# headamp.net
KiCad netlist of a schematic drawn in EAGLE
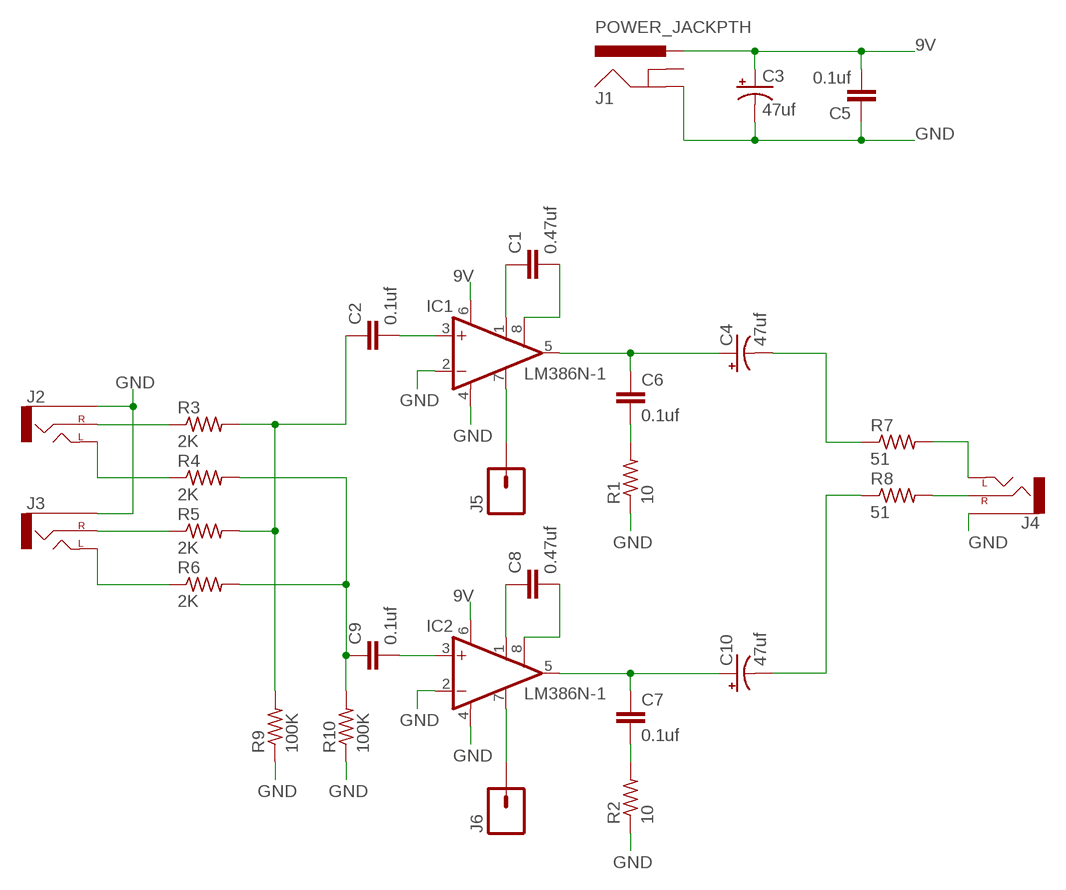
[diagram p0: schematic, sheet 1]

(export (version "E")
  (design (tool "Eeschema 10.0.6"))
  (components
    (comp (ref "C1")
      (value "0.47uf")
      (footprint "eagle-import:1210")
      (libsource (lib "eagle-import") (part "10UF50V20%(1210)"))
    )
    (comp (ref "C2")
      (value "0.1uf")
      (footprint "eagle-import:1210")
      (libsource (lib "eagle-import") (part "10UF50V20%(1210)"))
    )
    (comp (ref "C3")
      (value "47uf")
      (footprint "eagle-import:CPOL-RADIAL-100UF-25V")
      (libsource (lib "eagle-import") (part "100UF-25V-20%(PTH)"))
    )
    (comp (ref "C4")
      (value "47uf")
      (footprint "eagle-import:CPOL-RADIAL-100UF-25V")
      (libsource (lib "eagle-import") (part "100UF-25V-20%(PTH)"))
    )
    (comp (ref "C5")
      (value "0.1uf")
      (footprint "eagle-import:1210")
      (libsource (lib "eagle-import") (part "10UF50V20%(1210)"))
    )
    (comp (ref "C6")
      (value "0.1uf")
      (footprint "eagle-import:1210")
      (libsource (lib "eagle-import") (part "10UF50V20%(1210)"))
    )
    (comp (ref "C7")
      (value "0.1uf")
      (footprint "eagle-import:1210")
      (libsource (lib "eagle-import") (part "10UF50V20%(1210)"))
    )
    (comp (ref "C8")
      (value "0.47uf")
      (footprint "eagle-import:1210")
      (libsource (lib "eagle-import") (part "10UF50V20%(1210)"))
    )
    (comp (ref "C9")
      (value "0.1uf")
      (footprint "eagle-import:1210")
      (libsource (lib "eagle-import") (part "10UF50V20%(1210)"))
    )
    (comp (ref "C10")
      (value "47uf")
      (footprint "eagle-import:CPOL-RADIAL-100UF-25V")
      (libsource (lib "eagle-import") (part "100UF-25V-20%(PTH)"))
    )
    (comp (ref "IC1")
      (value "LM386N-1")
      (footprint "eagle-import:DIL08")
      (libsource (lib "eagle-import") (part "LM386?-N1"))
    )
    (comp (ref "IC2")
      (value "LM386N-1")
      (footprint "eagle-import:DIL08")
      (libsource (lib "eagle-import") (part "LM386?-N1"))
    )
    (comp (ref "J1")
      (value "POWER_JACKPTH")
      (footprint "eagle-import:POWER_JACK_PTH")
      (libsource (lib "eagle-import") (part "POWER_JACKPTH"))
    )
    (comp (ref "J2")
      (value "AUDIO-JACKPTH")
      (footprint "eagle-import:AUDIO-JACK")
      (libsource (lib "eagle-import") (part "AUDIO-JACKPTH"))
    )
    (comp (ref "J3")
      (value "AUDIO-JACKPTH")
      (footprint "eagle-import:AUDIO-JACK")
      (libsource (lib "eagle-import") (part "AUDIO-JACKPTH"))
    )
    (comp (ref "J4")
      (value "AUDIO-JACKPTH")
      (footprint "eagle-import:AUDIO-JACK")
      (libsource (lib "eagle-import") (part "AUDIO-JACKPTH"))
    )
    (comp (ref "J5")
      (value "M01NOSILK-KIT")
      (footprint "eagle-import:1X01NS-KIT")
      (libsource (lib "eagle-import") (part "M01NOSILK-KIT"))
    )
    (comp (ref "J6")
      (value "M01NOSILK-KIT")
      (footprint "eagle-import:1X01NS-KIT")
      (libsource (lib "eagle-import") (part "M01NOSILK-KIT"))
    )
    (comp (ref "R1")
      (value "10")
      (footprint "eagle-import:M0805")
      (libsource (lib "eagle-import") (part "R-US_M0805"))
    )
    (comp (ref "R2")
      (value "10")
      (footprint "eagle-import:M0805")
      (libsource (lib "eagle-import") (part "R-US_M0805"))
    )
    (comp (ref "R3")
      (value "2K")
      (footprint "eagle-import:M0805")
      (libsource (lib "eagle-import") (part "R-US_M0805"))
    )
    (comp (ref "R4")
      (value "2K")
      (footprint "eagle-import:M0805")
      (libsource (lib "eagle-import") (part "R-US_M0805"))
    )
    (comp (ref "R5")
      (value "2K")
      (footprint "eagle-import:M0805")
      (libsource (lib "eagle-import") (part "R-US_M0805"))
    )
    (comp (ref "R6")
      (value "2K")
      (footprint "eagle-import:M0805")
      (libsource (lib "eagle-import") (part "R-US_M0805"))
    )
    (comp (ref "R7")
      (value "51")
      (footprint "eagle-import:M0805")
      (libsource (lib "eagle-import") (part "R-US_M0805"))
    )
    (comp (ref "R8")
      (value "51")
      (footprint "eagle-import:M0805")
      (libsource (lib "eagle-import") (part "R-US_M0805"))
    )
    (comp (ref "R9")
      (value "100K")
      (footprint "eagle-import:M0805")
      (libsource (lib "eagle-import") (part "R-US_M0805"))
    )
    (comp (ref "R10")
      (value "100K")
      (footprint "eagle-import:M0805")
      (libsource (lib "eagle-import") (part "R-US_M0805"))
    )
  )
  (nets
    (net (code "1") (name "/9V") (class "Default")
      (node (ref "C3") (pin "1") (pinfunction "+_1") (pintype "passive"))
      (node (ref "C5") (pin "2") (pinfunction "2_2") (pintype "passive"))
      (node (ref "IC1") (pin "6") (pinfunction "VS_6") (pintype "power_in"))
      (node (ref "IC2") (pin "6") (pinfunction "VS_6") (pintype "power_in"))
      (node (ref "J1") (pin "PWR") (pinfunction "PWR_PWR") (pintype "bidirectional"))
    )
    (net (code "2") (name "/GND") (class "Default")
      (node (ref "C3") (pin "2") (pinfunction "-_2") (pintype "passive"))
      (node (ref "C5") (pin "1") (pinfunction "1_1") (pintype "passive"))
      (node (ref "IC1") (pin "2") (pinfunction "-IN_2") (pintype "input"))
      (node (ref "IC1") (pin "4") (pinfunction "GND_4") (pintype "power_in"))
      (node (ref "IC2") (pin "2") (pinfunction "-IN_2") (pintype "input"))
      (node (ref "IC2") (pin "4") (pinfunction "GND_4") (pintype "power_in"))
      (node (ref "J1") (pin "GND") (pinfunction "GND_GND") (pintype "bidirectional"))
      (node (ref "J2") (pin "SLEEVE") (pinfunction "SLEEVE_SLEEVE") (pintype "bidirectional"))
      (node (ref "J3") (pin "SLEEVE") (pinfunction "SLEEVE_SLEEVE") (pintype "bidirectional"))
      (node (ref "J4") (pin "SLEEVE") (pinfunction "SLEEVE_SLEEVE") (pintype "bidirectional"))
      (node (ref "R1") (pin "1") (pinfunction "1_1") (pintype "passive"))
      (node (ref "R10") (pin "1") (pinfunction "1_1") (pintype "passive"))
      (node (ref "R2") (pin "1") (pinfunction "1_1") (pintype "passive"))
      (node (ref "R9") (pin "1") (pinfunction "1_1") (pintype "passive"))
    )
    (net (code "3") (name "Net-(C1-Pad1)") (class "Default")
      (node (ref "C1") (pin "1") (pinfunction "1_1") (pintype "passive"))
      (node (ref "IC1") (pin "1") (pinfunction "GAIN_1") (pintype "passive"))
    )
    (net (code "4") (name "Net-(C1-Pad2)") (class "Default")
      (node (ref "C1") (pin "2") (pinfunction "2_2") (pintype "passive"))
      (node (ref "IC1") (pin "8") (pinfunction "GAIN_8") (pintype "passive"))
    )
    (net (code "5") (name "Net-(C2-Pad1)") (class "Default")
      (node (ref "C2") (pin "1") (pinfunction "1_1") (pintype "passive"))
      (node (ref "R3") (pin "2") (pinfunction "2_2") (pintype "passive"))
      (node (ref "R5") (pin "2") (pinfunction "2_2") (pintype "passive"))
      (node (ref "R9") (pin "2") (pinfunction "2_2") (pintype "passive"))
    )
    (net (code "6") (name "Net-(C4-+)") (class "Default")
      (node (ref "C4") (pin "1") (pinfunction "+_1") (pintype "passive"))
      (node (ref "C6") (pin "1") (pinfunction "1_1") (pintype "passive"))
      (node (ref "IC1") (pin "5") (pinfunction "OUT_5") (pintype "output"))
    )
    (net (code "7") (name "Net-(C4--)") (class "Default")
      (node (ref "C4") (pin "2") (pinfunction "-_2") (pintype "passive"))
      (node (ref "R7") (pin "1") (pinfunction "1_1") (pintype "passive"))
    )
    (net (code "8") (name "Net-(C6-Pad2)") (class "Default")
      (node (ref "C6") (pin "2") (pinfunction "2_2") (pintype "passive"))
      (node (ref "R1") (pin "2") (pinfunction "2_2") (pintype "passive"))
    )
    (net (code "9") (name "Net-(C7-Pad2)") (class "Default")
      (node (ref "C7") (pin "2") (pinfunction "2_2") (pintype "passive"))
      (node (ref "R2") (pin "2") (pinfunction "2_2") (pintype "passive"))
    )
    (net (code "10") (name "Net-(C8-Pad1)") (class "Default")
      (node (ref "C8") (pin "1") (pinfunction "1_1") (pintype "passive"))
      (node (ref "IC2") (pin "1") (pinfunction "GAIN_1") (pintype "passive"))
    )
    (net (code "11") (name "Net-(C8-Pad2)") (class "Default")
      (node (ref "C8") (pin "2") (pinfunction "2_2") (pintype "passive"))
      (node (ref "IC2") (pin "8") (pinfunction "GAIN_8") (pintype "passive"))
    )
    (net (code "12") (name "Net-(C9-Pad1)") (class "Default")
      (node (ref "C9") (pin "1") (pinfunction "1_1") (pintype "passive"))
      (node (ref "R10") (pin "2") (pinfunction "2_2") (pintype "passive"))
      (node (ref "R4") (pin "2") (pinfunction "2_2") (pintype "passive"))
      (node (ref "R6") (pin "2") (pinfunction "2_2") (pintype "passive"))
    )
    (net (code "13") (name "Net-(C10-+)") (class "Default")
      (node (ref "C10") (pin "1") (pinfunction "+_1") (pintype "passive"))
      (node (ref "C7") (pin "1") (pinfunction "1_1") (pintype "passive"))
      (node (ref "IC2") (pin "5") (pinfunction "OUT_5") (pintype "output"))
    )
    (net (code "14") (name "Net-(C10--)") (class "Default")
      (node (ref "C10") (pin "2") (pinfunction "-_2") (pintype "passive"))
      (node (ref "R8") (pin "1") (pinfunction "1_1") (pintype "passive"))
    )
    (net (code "15") (name "Net-(IC1-+IN)") (class "Default")
      (node (ref "C2") (pin "2") (pinfunction "2_2") (pintype "passive"))
      (node (ref "IC1") (pin "3") (pinfunction "+IN_3") (pintype "input"))
    )
    (net (code "16") (name "Net-(IC1-BYPASS)") (class "Default")
      (node (ref "IC1") (pin "7") (pinfunction "BYPASS_7") (pintype "passive"))
      (node (ref "J5") (pin "1") (pinfunction "1_1") (pintype "passive"))
    )
    (net (code "17") (name "Net-(IC2-+IN)") (class "Default")
      (node (ref "C9") (pin "2") (pinfunction "2_2") (pintype "passive"))
      (node (ref "IC2") (pin "3") (pinfunction "+IN_3") (pintype "input"))
    )
    (net (code "18") (name "Net-(IC2-BYPASS)") (class "Default")
      (node (ref "IC2") (pin "7") (pinfunction "BYPASS_7") (pintype "passive"))
      (node (ref "J6") (pin "1") (pinfunction "1_1") (pintype "passive"))
    )
    (net (code "19") (name "Net-(J2-LEFT)") (class "Default")
      (node (ref "J2") (pin "TIP") (pinfunction "LEFT_TIP") (pintype "bidirectional"))
      (node (ref "R4") (pin "1") (pinfunction "1_1") (pintype "passive"))
    )
    (net (code "20") (name "Net-(J2-RIGHT)") (class "Default")
      (node (ref "J2") (pin "RING") (pinfunction "RIGHT_RING") (pintype "bidirectional"))
      (node (ref "R3") (pin "1") (pinfunction "1_1") (pintype "passive"))
    )
    (net (code "21") (name "Net-(J3-LEFT)") (class "Default")
      (node (ref "J3") (pin "TIP") (pinfunction "LEFT_TIP") (pintype "bidirectional"))
      (node (ref "R6") (pin "1") (pinfunction "1_1") (pintype "passive"))
    )
    (net (code "22") (name "Net-(J3-RIGHT)") (class "Default")
      (node (ref "J3") (pin "RING") (pinfunction "RIGHT_RING") (pintype "bidirectional"))
      (node (ref "R5") (pin "1") (pinfunction "1_1") (pintype "passive"))
    )
    (net (code "23") (name "Net-(J4-LEFT)") (class "Default")
      (node (ref "J4") (pin "TIP") (pinfunction "LEFT_TIP") (pintype "bidirectional"))
      (node (ref "R7") (pin "2") (pinfunction "2_2") (pintype "passive"))
    )
    (net (code "24") (name "Net-(J4-RIGHT)") (class "Default")
      (node (ref "J4") (pin "RING") (pinfunction "RIGHT_RING") (pintype "bidirectional"))
      (node (ref "R8") (pin "2") (pinfunction "2_2") (pintype "passive"))
    )
    (net (code "25") (name "unconnected-(J1-PadGNDBREAK)") (class "Default")
      (node (ref "J1") (pin "GNDBREAK") (pinfunction "GNDBREAK_GNDBREAK") (pintype "bidirectional"))
    )
  )
)
